# 52_MIPI_Panel.net
KiCad netlist of a schematic drawn in Altium Designer
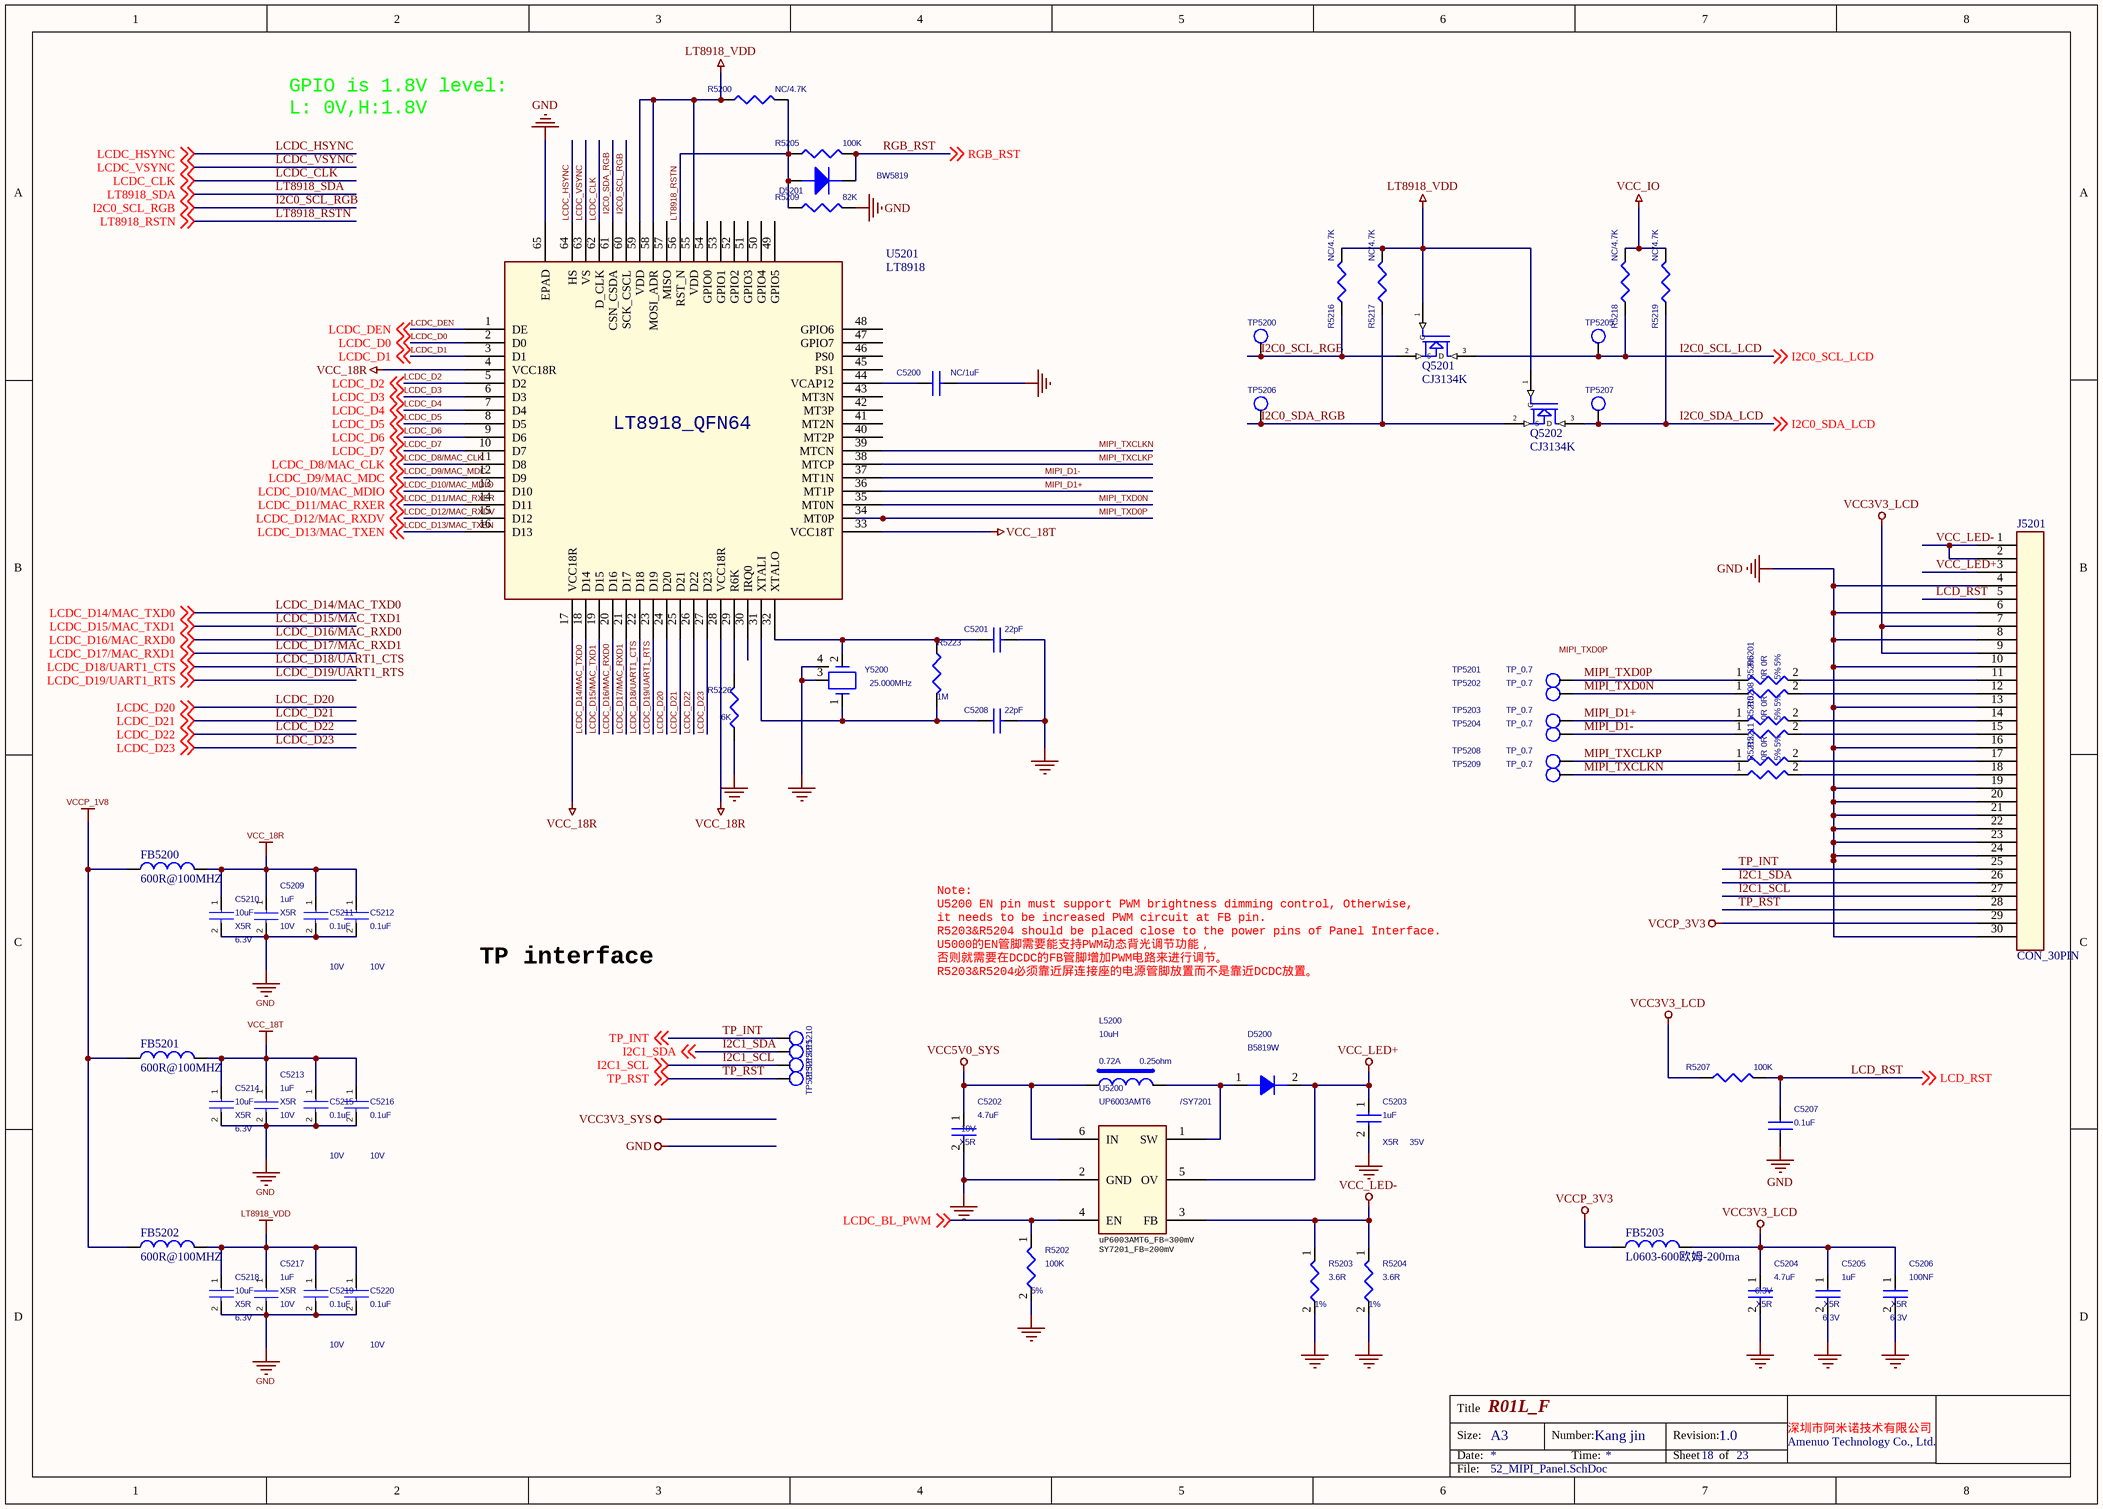
[diagram p0: 52_MIPI_Panel.SchDoc]

(export (version "E")
  (design (tool "Eeschema 10.0.6"))
  (components
    (comp (ref "C5200")
      (value "NC/1uF")
      (footprint "C0402")
      (fields (field (name "PART NUMBER") "117-00-3040") (field (name "DESIGNER") "Hujin"))
      (libsource (lib "*") (part "CAP_NP0603"))
    )
    (comp (ref "C5201")
      (value "22pF")
      (footprint "C0402")
      (fields (field (name "PART NUMBER") "117-00-3002") (field (name "DESIGNER") "Hujin"))
      (libsource (lib "*") (part "CAP_NP0603_Dup1"))
    )
    (comp (ref "C5202")
      (value "4.7uF")
      (footprint "C0603")
      (description "cap,4.70uF,+/-10%,10V,X5R,C0603")
      (fields
        (field (name "VOLTAGE") "10V")
        (field (name "DIELECTRIC") "X5R")
        (field (name "MANUFACTURER") "TDK")
        (field (name "TOLERANCE") "10%")
        (field (name "CREATED BY") "JJJ")
      )
      (libsource (lib "*") (part "CAP NP_Dup1"))
    )
    (comp (ref "C5203")
      (value "1uF")
      (footprint "C0402")
      (description "cap,1.00uF,+/-10%,35V,X5R,C0402")
      (fields
        (field (name "VOLTAGE") "35V")
        (field (name "DIELECTRIC") "X5R")
        (field (name "MANUFACTURER") "TDK")
        (field (name "TOLERANCE") "10%")
        (field (name "CREATED BY") "JJJ")
      )
      (libsource (lib "*") (part "CAP NP_Dup1"))
    )
    (comp (ref "C5204")
      (value "4.7uF")
      (footprint "C0402")
      (description "cap,4.70uF,+/-10%,6.3V,X5R,C0402")
      (fields
        (field (name "VOLTAGE") "6.3V")
        (field (name "DIELECTRIC") "X5R")
        (field (name "TOLERANCE") "10%")
        (field (name "MANUFACTURER") "TDK")
        (field (name "CREATED BY") "JJJ")
      )
      (libsource (lib "*") (part "CAP NP_Dup1"))
    )
    (comp (ref "C5205")
      (value "1uF")
      (footprint "C0402")
      (description "cap,1.00uF,+/-10%,6.3V,X5R,C0402")
      (fields
        (field (name "VOLTAGE") "6.3V")
        (field (name "DIELECTRIC") "X5R")
        (field (name "MANUFACTURER") "TDK")
        (field (name "TOLERANCE") "10%")
        (field (name "CREATED BY") "JJJ")
      )
      (libsource (lib "*") (part "CAP NP_Dup1"))
    )
    (comp (ref "C5206")
      (value "100NF")
      (footprint "C0402")
      (description "cap,100.00nF,+/-10%,6.3V,X5R,C0402")
      (fields
        (field (name "VOLTAGE") "6.3V")
        (field (name "DIELECTRIC") "X5R")
        (field (name "MANUFACTURER") "TDK")
        (field (name "TOLERANCE") "10%")
        (field (name "CREATED BY") "JJJ")
      )
      (libsource (lib "*") (part "CAP NP_Dup1"))
    )
    (comp (ref "C5207")
      (value "0.1uF")
      (footprint "C0402")
      (description "贴片电容")
      (libsource (lib "") (part "CAP NP_Dup1_1"))
    )
    (comp (ref "C5208")
      (value "22pF")
      (footprint "C0402")
      (fields (field (name "PART NUMBER") "117-00-3002") (field (name "DESIGNER") "Hujin"))
      (libsource (lib "*") (part "CAP_NP0603_Dup1"))
    )
    (comp (ref "C5209")
      (value "1uF")
      (footprint "C0402")
      (description "cap,1.00uF,+/-10%,10V,X5R,C0402")
      (fields
        (field (name "VOLTAGE") "10V")
        (field (name "MANUFACTURER") "TDK")
        (field (name "TOLERANCE") "10%")
        (field (name "DIELECTRIC") "X5R")
        (field (name "CREATED_BY") "JJJ")
      )
      (libsource (lib "*") (part "CAP_NP_2"))
    )
    (comp (ref "C5210")
      (value "10uF")
      (footprint "C0603")
      (description "cap,10.00uF,+/-10%,6.3V,X5R,C0603")
      (fields
        (field (name "DIELECTRIC") "X5R")
        (field (name "VOLTAGE") "6.3V")
        (field (name "TOLERANCE") "10%")
        (field (name "MANUFACTURER") "TDK")
        (field (name "CREATED_BY") "JJJ")
      )
      (libsource (lib "*") (part "CAP_NP_2"))
    )
    (comp (ref "C5211")
      (value "0.1uF")
      (footprint "C0402")
      (description "cap,0.1uF,+/-10%,10V,X5R,C0402")
      (fields
        (field (name "TOLERANCE") "10%")
        (field (name "MANUFACTURER") "TDK")
        (field (name "VOLTAGE") "10V")
        (field (name "CREATED_BY") "JJJ")
      )
      (libsource (lib "*") (part "CAP_NP_2"))
    )
    (comp (ref "C5212")
      (value "0.1uF")
      (footprint "C0402")
      (description "cap,0.1uF,+/-10%,10V,X5R,C0402")
      (fields
        (field (name "TOLERANCE") "10%")
        (field (name "MANUFACTURER") "TDK")
        (field (name "VOLTAGE") "10V")
        (field (name "CREATED_BY") "JJJ")
      )
      (libsource (lib "*") (part "CAP_NP_2"))
    )
    (comp (ref "C5213")
      (value "1uF")
      (footprint "C0402")
      (description "cap,1.00uF,+/-10%,10V,X5R,C0402")
      (fields
        (field (name "VOLTAGE") "10V")
        (field (name "MANUFACTURER") "TDK")
        (field (name "TOLERANCE") "10%")
        (field (name "DIELECTRIC") "X5R")
        (field (name "CREATED_BY") "JJJ")
      )
      (libsource (lib "*") (part "CAP_NP_2"))
    )
    (comp (ref "C5214")
      (value "10uF")
      (footprint "C0603")
      (description "cap,10.00uF,+/-10%,6.3V,X5R,C0603")
      (fields
        (field (name "DIELECTRIC") "X5R")
        (field (name "VOLTAGE") "6.3V")
        (field (name "TOLERANCE") "10%")
        (field (name "MANUFACTURER") "TDK")
        (field (name "CREATED_BY") "JJJ")
      )
      (libsource (lib "*") (part "CAP_NP_2"))
    )
    (comp (ref "C5215")
      (value "0.1uF")
      (footprint "C0402")
      (description "cap,0.1uF,+/-10%,10V,X5R,C0402")
      (fields
        (field (name "TOLERANCE") "10%")
        (field (name "MANUFACTURER") "TDK")
        (field (name "VOLTAGE") "10V")
        (field (name "CREATED_BY") "JJJ")
      )
      (libsource (lib "*") (part "CAP_NP_2"))
    )
    (comp (ref "C5216")
      (value "0.1uF")
      (footprint "C0402")
      (description "cap,0.1uF,+/-10%,10V,X5R,C0402")
      (fields
        (field (name "TOLERANCE") "10%")
        (field (name "MANUFACTURER") "TDK")
        (field (name "VOLTAGE") "10V")
        (field (name "CREATED_BY") "JJJ")
      )
      (libsource (lib "*") (part "CAP_NP_2"))
    )
    (comp (ref "C5217")
      (value "1uF")
      (footprint "C0402")
      (description "cap,1.00uF,+/-10%,10V,X5R,C0402")
      (fields
        (field (name "VOLTAGE") "10V")
        (field (name "MANUFACTURER") "TDK")
        (field (name "TOLERANCE") "10%")
        (field (name "DIELECTRIC") "X5R")
        (field (name "CREATED_BY") "JJJ")
      )
      (libsource (lib "*") (part "CAP_NP_2"))
    )
    (comp (ref "C5218")
      (value "10uF")
      (footprint "C0603")
      (description "cap,10.00uF,+/-10%,6.3V,X5R,C0603")
      (fields
        (field (name "DIELECTRIC") "X5R")
        (field (name "VOLTAGE") "6.3V")
        (field (name "TOLERANCE") "10%")
        (field (name "MANUFACTURER") "TDK")
        (field (name "CREATED_BY") "JJJ")
      )
      (libsource (lib "*") (part "CAP_NP_2"))
    )
    (comp (ref "C5219")
      (value "0.1uF")
      (footprint "C0402")
      (description "cap,0.1uF,+/-10%,10V,X5R,C0402")
      (fields
        (field (name "TOLERANCE") "10%")
        (field (name "MANUFACTURER") "TDK")
        (field (name "VOLTAGE") "10V")
        (field (name "CREATED_BY") "JJJ")
      )
      (libsource (lib "*") (part "CAP_NP_2"))
    )
    (comp (ref "C5220")
      (value "0.1uF")
      (footprint "C0402")
      (description "cap,0.1uF,+/-10%,10V,X5R,C0402")
      (fields
        (field (name "TOLERANCE") "10%")
        (field (name "MANUFACTURER") "TDK")
        (field (name "VOLTAGE") "10V")
        (field (name "CREATED_BY") "JJJ")
      )
      (libsource (lib "*") (part "CAP_NP_2"))
    )
    (comp (ref "D5200")
      (value "B5819W")
      (footprint "SOD123")
      (description "Schottky Barrier，B5819W SOD-123")
      (fields (field (name "MANUFACTURER") "长电") (field (name "CREATED BY") "JJJ"))
      (libsource (lib "*") (part "DIODE_Dup1"))
    )
    (comp (ref "D5201")
      (value "BW5819")
      (footprint "SOD-323")
      (description "Diode DO-214AA SMA")
      (fields (field (name "MANUFACTURER") "Diodes") (field (name "MANUFACTURER PART NUMBER") "B220/A"))
      (libsource (lib "*") (part "DIODE"))
    )
    (comp (ref "FB5200")
      (value "600R@100MHZ")
      (footprint "L0402")
      (description "磁珠;600R@100MHZ;0.34R;0.45A;0402;贴片;")
      (libsource (lib "amenuo") (part "INDUCTOR"))
    )
    (comp (ref "FB5201")
      (value "600R@100MHZ")
      (footprint "L0402")
      (description "磁珠;600R@100MHZ;0.34R;0.45A;0402;贴片;")
      (libsource (lib "amenuo") (part "INDUCTOR"))
    )
    (comp (ref "FB5202")
      (value "600R@100MHZ")
      (footprint "L0402")
      (description "磁珠;600R@100MHZ;0.34R;0.45A;0402;贴片;")
      (libsource (lib "amenuo") (part "INDUCTOR"))
    )
    (comp (ref "FB5203")
      (value "L0603-600欧姆-200ma")
      (footprint "L0402")
      (description "L0603-0欧姆-1A")
      (libsource (lib "amenuo") (part "INDUCTOR"))
    )
    (comp (ref "J5201")
      (value "CON_30PIN")
      (footprint "X05A10H30G")
      (libsource (lib "amenuo") (part "CON_30PIN"))
    )
    (comp (ref "L5200")
      (value "10uH")
      (footprint "IND-3X3")
      (description "Power Inductor,10uH,0.2,IND_303015")
      (fields
        (field (name "DC RESISTOR") "0.25ohm")
        (field (name "ISAT") "0.72A")
        (field (name "MANUFACTURER") "sunlord")
        (field (name "TOLERANCE") "20%")
        (field (name "CREATED BY") "YTL")
      )
      (libsource (lib "*") (part "INDUCTORS OF FERRITE"))
    )
    (comp (ref "Q5201") (value "CJ3134K") (footprint "SOT23") (libsource (lib "amenuo") (part "MOSFET-2S3D")))
    (comp (ref "Q5202") (value "CJ3134K") (footprint "SOT23") (libsource (lib "amenuo") (part "MOSFET-2S3D")))
    (comp (ref "R5200")
      (value "NC/4.7K")
      (footprint "R0402")
      (description "贴片电阻")
      (libsource (lib "*") (part "RESISTOR_1"))
    )
    (comp (ref "R5201")
      (value "0R")
      (footprint "R0402")
      (description "通用厚膜电阻,0R,+/-5%,R0402,1/16W.")
      (fields
        (field (name "TOLERANCE") "5%")
        (field (name "MANUFACTURER") "YAGEO")
        (field (name "CREATED BY") "YTL")
      )
      (libsource (lib "*") (part "RESISTOR_Dup1"))
    )
    (comp (ref "R5202")
      (value "100K")
      (footprint "R0402")
      (description "通用厚膜电阻,100K,+/-5%,R0402,1/16W.")
      (fields
        (field (name "TOLERANCE") "5%")
        (field (name "MANUFACTURER") "YAGEO")
        (field (name "CREATED BY") "YTL")
      )
      (libsource (lib "*") (part "RESISTOR_Dup1"))
    )
    (comp (ref "R5203")
      (value "3.6R")
      (footprint "R0402")
      (description "通用厚膜电阻,3R6,+/-1%,R0603,1/10W.")
      (fields
        (field (name "TOLERANCE") "1%")
        (field (name "MANUFACTURER") "YAGEO")
        (field (name "CREATED BY") "YTL")
      )
      (libsource (lib "*") (part "RESISTOR_Dup1"))
    )
    (comp (ref "R5204")
      (value "3.6R")
      (footprint "R0402")
      (description "通用厚膜电阻,3R6,+/-1%,R0603,1/10W.")
      (fields
        (field (name "TOLERANCE") "1%")
        (field (name "MANUFACTURER") "YAGEO")
        (field (name "CREATED BY") "YTL")
      )
      (libsource (lib "*") (part "RESISTOR_Dup1"))
    )
    (comp (ref "R5205")
      (value "100K")
      (footprint "R0402")
      (description "贴片电阻")
      (libsource (lib "*") (part "RESISTOR_1"))
    )
    (comp (ref "R5206")
      (value "0R")
      (footprint "R0402")
      (description "通用厚膜电阻,0R,+/-5%,R0402,1/16W.")
      (fields
        (field (name "TOLERANCE") "5%")
        (field (name "MANUFACTURER") "YAGEO")
        (field (name "CREATED BY") "YTL")
      )
      (libsource (lib "*") (part "RESISTOR_Dup1"))
    )
    (comp (ref "R5207")
      (value "100K")
      (footprint "R0402")
      (description "贴片电阻")
      (libsource (lib "*") (part "RESISTOR_1"))
    )
    (comp (ref "R5208")
      (value "0R")
      (footprint "R0402")
      (description "通用厚膜电阻,0R,+/-5%,R0402,1/16W.")
      (fields
        (field (name "TOLERANCE") "5%")
        (field (name "MANUFACTURER") "YAGEO")
        (field (name "CREATED BY") "YTL")
      )
      (libsource (lib "*") (part "RESISTOR_Dup1"))
    )
    (comp (ref "R5209")
      (value "82K")
      (footprint "R0402")
      (description "贴片电阻")
      (libsource (lib "*") (part "RESISTOR_1"))
    )
    (comp (ref "R5210")
      (value "0R")
      (footprint "R0402")
      (description "通用厚膜电阻,0R,+/-5%,R0402,1/16W.")
      (fields
        (field (name "TOLERANCE") "5%")
        (field (name "MANUFACTURER") "YAGEO")
        (field (name "CREATED BY") "YTL")
      )
      (libsource (lib "*") (part "RESISTOR_Dup1"))
    )
    (comp (ref "R5211")
      (value "0R")
      (footprint "R0402")
      (description "通用厚膜电阻,0R,+/-5%,R0402,1/16W.")
      (fields
        (field (name "TOLERANCE") "5%")
        (field (name "MANUFACTURER") "YAGEO")
        (field (name "CREATED BY") "YTL")
      )
      (libsource (lib "*") (part "RESISTOR_Dup1"))
    )
    (comp (ref "R5212")
      (value "0R")
      (footprint "R0402")
      (description "通用厚膜电阻,0R,+/-5%,R0402,1/16W.")
      (fields
        (field (name "TOLERANCE") "5%")
        (field (name "MANUFACTURER") "YAGEO")
        (field (name "CREATED BY") "YTL")
      )
      (libsource (lib "*") (part "RESISTOR_Dup1"))
    )
    (comp (ref "R5216")
      (value "NC/4.7K")
      (footprint "R0402")
      (description "贴片电阻")
      (libsource (lib "*") (part "RESISTOR_1"))
    )
    (comp (ref "R5217")
      (value "NC/4.7K")
      (footprint "R0402")
      (description "贴片电阻")
      (libsource (lib "*") (part "RESISTOR_1"))
    )
    (comp (ref "R5218")
      (value "NC/4.7K")
      (footprint "R0402")
      (description "贴片电阻")
      (libsource (lib "*") (part "RESISTOR_1"))
    )
    (comp (ref "R5219")
      (value "NC/4.7K")
      (footprint "R0402")
      (description "贴片电阻")
      (libsource (lib "*") (part "RESISTOR_1"))
    )
    (comp (ref "R5223")
      (value "1M")
      (footprint "R0402")
      (fields (field (name "PART NUMBER") "737-00-3074") (field (name "DESIGNER") "Hujin"))
      (libsource (lib "*") (part "RES0603_Dup3"))
    )
    (comp (ref "R5226")
      (value "6K")
      (footprint "R0402")
      (fields
        (field (name "TOLERANCE") "%5")
        (field (name "PART NUMBER") "737-00-3049")
        (field (name "DESIGNER") "Hujin")
      )
      (libsource (lib "*") (part "RES0603_Dup2"))
    )
    (comp (ref "TP5200")
      (value "TP_0.7")
      (footprint "TEST")
      (description "Test Point 0.7mm")
      (fields (field (name "CREATED BY") "JJJ"))
      (libsource (lib "*") (part "TP"))
    )
    (comp (ref "TP5201")
      (value "TP_0.7")
      (footprint "TP")
      (fields (field (name "CREATED BY") "JJJ"))
      (libsource (lib "*") (part "TP"))
    )
    (comp (ref "TP5202")
      (value "TP_0.7")
      (footprint "TP")
      (fields (field (name "CREATED BY") "JJJ"))
      (libsource (lib "*") (part "TP"))
    )
    (comp (ref "TP5203")
      (value "TP_0.7")
      (footprint "TP")
      (fields (field (name "CREATED BY") "JJJ"))
      (libsource (lib "*") (part "TP"))
    )
    (comp (ref "TP5204")
      (value "TP_0.7")
      (footprint "TP")
      (fields (field (name "CREATED BY") "JJJ"))
      (libsource (lib "*") (part "TP"))
    )
    (comp (ref "TP5205")
      (value "TP_0.7")
      (footprint "TEST")
      (description "Test Point 0.7mm")
      (fields (field (name "CREATED BY") "JJJ"))
      (libsource (lib "*") (part "TP"))
    )
    (comp (ref "TP5206")
      (value "TP_0.7")
      (footprint "TEST")
      (description "Test Point 0.7mm")
      (fields (field (name "CREATED BY") "JJJ"))
      (libsource (lib "*") (part "TP"))
    )
    (comp (ref "TP5207")
      (value "TP_0.7")
      (footprint "TEST")
      (description "Test Point 0.7mm")
      (fields (field (name "CREATED BY") "JJJ"))
      (libsource (lib "*") (part "TP"))
    )
    (comp (ref "TP5208")
      (value "TP_0.7")
      (footprint "TP")
      (fields (field (name "CREATED BY") "JJJ"))
      (libsource (lib "*") (part "TP"))
    )
    (comp (ref "TP5209")
      (value "TP_0.7")
      (footprint "TP")
      (fields (field (name "CREATED BY") "JJJ"))
      (libsource (lib "*") (part "TP"))
    )
    (comp (ref "TP5210")
      (value "TP_0.7")
      (footprint "TEST")
      (description "Test Point 0.7mm")
      (fields (field (name "CREATED BY") "JJJ"))
      (libsource (lib "*") (part "TP"))
    )
    (comp (ref "TP5211")
      (value "TP_0.7")
      (footprint "TEST")
      (description "Test Point 0.7mm")
      (fields (field (name "CREATED BY") "JJJ"))
      (libsource (lib "*") (part "TP"))
    )
    (comp (ref "TP5212")
      (value "TP_0.7")
      (footprint "TEST")
      (description "Test Point 0.7mm")
      (fields (field (name "CREATED BY") "JJJ"))
      (libsource (lib "*") (part "TP"))
    )
    (comp (ref "TP5213")
      (value "TP_0.7")
      (footprint "TEST")
      (description "Test Point 0.7mm")
      (fields (field (name "CREATED BY") "JJJ"))
      (libsource (lib "*") (part "TP"))
    )
    (comp (ref "U5200")
      (value "UP6003AMT6")
      (footprint "SOT-23-6")
      (description "Tiny Package, High Performance, Constant Current Switching Regulator for 10X White LED")
      (fields
        (field (name "MANUFACTURER") "UPI(力智电子)")
        (field (name "OPTION") "/SY7201")
        (field (name "CREATED BY") "JJJ")
      )
      (libsource (lib "*") (part "DCDC_MP1488"))
    )
    (comp (ref "U5201")
      (value "LT8918")
      (footprint "LT8918_QFN64_EPAD")
      (libsource (lib "amenuo") (part "LT8918"))
    )
    (comp (ref "Y5200") (value "25.000MHz") (footprint "SMD_3225") (libsource (lib "*") (part "CRYSTAL_0")))
  )
  (nets
    (net (code "1") (name "/I2C0_SDA_RGB") (class "Default")
      (node (ref "Q5202") (pin "2") (pinfunction "S_2") (pintype "input"))
      (node (ref "R5217") (pin "1") (pinfunction "1_1") (pintype "passive"))
      (node (ref "TP5206") (pin "1") (pinfunction "1_1") (pintype "passive"))
      (node (ref "U5201") (pin "61") (pinfunction "CSN_CSDA_61") (pintype "passive"))
    )
    (net (code "2") (name "/MIPI_D1+") (class "Default")
      (node (ref "R5208") (pin "1") (pinfunction "1_1") (pintype "passive"))
      (node (ref "TP5203") (pin "1") (pinfunction "1_1") (pintype "passive"))
      (node (ref "U5201") (pin "36") (pinfunction "MT1P_36") (pintype "passive"))
    )
    (net (code "3") (name "/MIPI_D1-") (class "Default")
      (node (ref "R5210") (pin "1") (pinfunction "1_1") (pintype "passive"))
      (node (ref "TP5204") (pin "1") (pinfunction "1_1") (pintype "passive"))
      (node (ref "U5201") (pin "37") (pinfunction "MT1N_37") (pintype "passive"))
    )
    (net (code "4") (name "/MIPI_TXCLKN") (class "Default")
      (node (ref "R5212") (pin "1") (pinfunction "1_1") (pintype "passive"))
      (node (ref "TP5209") (pin "1") (pinfunction "1_1") (pintype "passive"))
      (node (ref "U5201") (pin "39") (pinfunction "MTCN_39") (pintype "passive"))
    )
    (net (code "5") (name "/MIPI_TXCLKP") (class "Default")
      (node (ref "R5211") (pin "1") (pinfunction "1_1") (pintype "passive"))
      (node (ref "TP5208") (pin "1") (pinfunction "1_1") (pintype "passive"))
      (node (ref "U5201") (pin "38") (pinfunction "MTCP_38") (pintype "passive"))
    )
    (net (code "6") (name "/MIPI_TXD0N") (class "Default")
      (node (ref "R5206") (pin "1") (pinfunction "1_1") (pintype "passive"))
      (node (ref "TP5202") (pin "1") (pinfunction "1_1") (pintype "passive"))
      (node (ref "U5201") (pin "35") (pinfunction "MT0N_35") (pintype "passive"))
    )
    (net (code "7") (name "/MIPI_TXD0P") (class "Default")
      (node (ref "R5201") (pin "1") (pinfunction "1_1") (pintype "passive"))
      (node (ref "TP5201") (pin "1") (pinfunction "1_1") (pintype "passive"))
      (node (ref "U5201") (pin "34") (pinfunction "MT0P_34") (pintype "passive"))
    )
    (net (code "8") (name "GND") (class "Default")
      (node (ref "C5200") (pin "2") (pinfunction "2_2") (pintype "passive"))
      (node (ref "C5201") (pin "2") (pinfunction "2_2") (pintype "passive"))
      (node (ref "C5202") (pin "2") (pinfunction "2_2") (pintype "passive"))
      (node (ref "C5203") (pin "2") (pinfunction "2_2") (pintype "passive"))
      (node (ref "C5204") (pin "2") (pinfunction "2_2") (pintype "passive"))
      (node (ref "C5205") (pin "2") (pinfunction "2_2") (pintype "passive"))
      (node (ref "C5206") (pin "2") (pinfunction "2_2") (pintype "passive"))
      (node (ref "C5207") (pin "2") (pinfunction "2_2") (pintype "passive"))
      (node (ref "C5208") (pin "2") (pinfunction "2_2") (pintype "passive"))
      (node (ref "C5209") (pin "2") (pinfunction "2_2") (pintype "passive"))
      (node (ref "C5210") (pin "2") (pinfunction "2_2") (pintype "passive"))
      (node (ref "C5211") (pin "2") (pinfunction "2_2") (pintype "passive"))
      (node (ref "C5212") (pin "2") (pinfunction "2_2") (pintype "passive"))
      (node (ref "C5213") (pin "2") (pinfunction "2_2") (pintype "passive"))
      (node (ref "C5214") (pin "2") (pinfunction "2_2") (pintype "passive"))
      (node (ref "C5215") (pin "2") (pinfunction "2_2") (pintype "passive"))
      (node (ref "C5216") (pin "2") (pinfunction "2_2") (pintype "passive"))
      (node (ref "C5217") (pin "2") (pinfunction "2_2") (pintype "passive"))
      (node (ref "C5218") (pin "2") (pinfunction "2_2") (pintype "passive"))
      (node (ref "C5219") (pin "2") (pinfunction "2_2") (pintype "passive"))
      (node (ref "C5220") (pin "2") (pinfunction "2_2") (pintype "passive"))
      (node (ref "J5201") (pin "10") (pinfunction "10_10") (pintype "passive"))
      (node (ref "J5201") (pin "13") (pinfunction "13_13") (pintype "passive"))
      (node (ref "J5201") (pin "16") (pinfunction "16_16") (pintype "passive"))
      (node (ref "J5201") (pin "19") (pinfunction "19_19") (pintype "passive"))
      (node (ref "J5201") (pin "20") (pinfunction "20_20") (pintype "passive"))
      (node (ref "J5201") (pin "21") (pinfunction "21_21") (pintype "passive"))
      (node (ref "J5201") (pin "22") (pinfunction "22_22") (pintype "passive"))
      (node (ref "J5201") (pin "23") (pinfunction "23_23") (pintype "passive"))
      (node (ref "J5201") (pin "24") (pinfunction "24_24") (pintype "passive"))
      (node (ref "J5201") (pin "30") (pinfunction "30_30") (pintype "passive"))
      (node (ref "J5201") (pin "4") (pinfunction "4_4") (pintype "passive"))
      (node (ref "J5201") (pin "6") (pinfunction "6_6") (pintype "passive"))
      (node (ref "J5201") (pin "8") (pinfunction "8_8") (pintype "passive"))
      (node (ref "R5202") (pin "2") (pinfunction "2_2") (pintype "passive"))
      (node (ref "R5203") (pin "2") (pinfunction "2_2") (pintype "passive"))
      (node (ref "R5204") (pin "2") (pinfunction "2_2") (pintype "passive"))
      (node (ref "R5209") (pin "2") (pinfunction "2_2") (pintype "passive"))
      (node (ref "R5226") (pin "1") (pinfunction "1_1") (pintype "passive"))
      (node (ref "U5200") (pin "2") (pinfunction "GND_2") (pintype "passive"))
      (node (ref "U5201") (pin "65") (pinfunction "EPAD_65") (pintype "power_in"))
      (node (ref "Y5200") (pin "3") (pinfunction "3_3") (pintype "passive"))
      (node (ref "Y5200") (pin "4") (pinfunction "4_4") (pintype "passive"))
    )
    (net (code "9") (name "I2C0_SCL_LCD") (class "Default")
      (node (ref "Q5201") (pin "3") (pinfunction "D_3") (pintype "input"))
      (node (ref "R5218") (pin "1") (pinfunction "1_1") (pintype "passive"))
      (node (ref "TP5205") (pin "1") (pinfunction "1_1") (pintype "passive"))
    )
    (net (code "10") (name "I2C0_SCL_RGB") (class "Default")
      (node (ref "Q5201") (pin "2") (pinfunction "S_2") (pintype "input"))
      (node (ref "R5216") (pin "1") (pinfunction "1_1") (pintype "passive"))
      (node (ref "TP5200") (pin "1") (pinfunction "1_1") (pintype "passive"))
      (node (ref "U5201") (pin "60") (pinfunction "SCK_CSCL_60") (pintype "passive"))
    )
    (net (code "11") (name "I2C0_SDA_LCD") (class "Default")
      (node (ref "Q5202") (pin "3") (pinfunction "D_3") (pintype "input"))
      (node (ref "R5219") (pin "1") (pinfunction "1_1") (pintype "passive"))
      (node (ref "TP5207") (pin "1") (pinfunction "1_1") (pintype "passive"))
    )
    (net (code "12") (name "I2C1_SCL") (class "Default")
      (node (ref "J5201") (pin "27") (pinfunction "27_27") (pintype "passive"))
      (node (ref "TP5212") (pin "1") (pinfunction "1_1") (pintype "passive"))
    )
    (net (code "13") (name "I2C1_SDA") (class "Default")
      (node (ref "J5201") (pin "26") (pinfunction "26_26") (pintype "passive"))
      (node (ref "TP5211") (pin "1") (pinfunction "1_1") (pintype "passive"))
    )
    (net (code "14") (name "LCDC_BL_PWM") (class "Default")
      (node (ref "R5202") (pin "1") (pinfunction "1_1") (pintype "passive"))
      (node (ref "U5200") (pin "4") (pinfunction "EN_4") (pintype "passive"))
    )
    (net (code "15") (name "LCDC_CLK") (class "Default")
      (node (ref "U5201") (pin "62") (pinfunction "D_CLK_62") (pintype "power_in"))
    )
    (net (code "16") (name "LCDC_D0") (class "Default")
      (node (ref "U5201") (pin "2") (pinfunction "D0_2") (pintype "passive"))
    )
    (net (code "17") (name "LCDC_D1") (class "Default")
      (node (ref "U5201") (pin "3") (pinfunction "D1_3") (pintype "power_in"))
    )
    (net (code "18") (name "LCDC_D2") (class "Default")
      (node (ref "U5201") (pin "5") (pinfunction "D2_5") (pintype "passive"))
    )
    (net (code "19") (name "LCDC_D3") (class "Default")
      (node (ref "U5201") (pin "6") (pinfunction "D3_6") (pintype "passive"))
    )
    (net (code "20") (name "LCDC_D4") (class "Default")
      (node (ref "U5201") (pin "7") (pinfunction "D4_7") (pintype "passive"))
    )
    (net (code "21") (name "LCDC_D5") (class "Default")
      (node (ref "U5201") (pin "8") (pinfunction "D5_8") (pintype "passive"))
    )
    (net (code "22") (name "LCDC_D6") (class "Default")
      (node (ref "U5201") (pin "9") (pinfunction "D6_9") (pintype "passive"))
    )
    (net (code "23") (name "LCDC_D7") (class "Default")
      (node (ref "U5201") (pin "10") (pinfunction "D7_10") (pintype "passive"))
    )
    (net (code "24") (name "LCDC_D8{slash}MAC_CLK") (class "Default")
      (node (ref "U5201") (pin "11") (pinfunction "D8_11") (pintype "passive"))
    )
    (net (code "25") (name "LCDC_D9{slash}MAC_MDC") (class "Default")
      (node (ref "U5201") (pin "12") (pinfunction "D9_12") (pintype "passive"))
    )
    (net (code "26") (name "LCDC_D10{slash}MAC_MDIO") (class "Default")
      (node (ref "U5201") (pin "13") (pinfunction "D10_13") (pintype "passive"))
    )
    (net (code "27") (name "LCDC_D11{slash}MAC_RXER") (class "Default")
      (node (ref "U5201") (pin "14") (pinfunction "D11_14") (pintype "passive"))
    )
    (net (code "28") (name "LCDC_D12{slash}MAC_RXDV") (class "Default")
      (node (ref "U5201") (pin "15") (pinfunction "D12_15") (pintype "passive"))
    )
    (net (code "29") (name "LCDC_D13{slash}MAC_TXEN") (class "Default")
      (node (ref "U5201") (pin "16") (pinfunction "D13_16") (pintype "passive"))
    )
    (net (code "30") (name "LCDC_D14{slash}MAC_TXD0") (class "Default")
      (node (ref "U5201") (pin "18") (pinfunction "D14_18") (pintype "passive"))
    )
    (net (code "31") (name "LCDC_D15{slash}MAC_TXD1") (class "Default")
      (node (ref "U5201") (pin "19") (pinfunction "D15_19") (pintype "passive"))
    )
    (net (code "32") (name "LCDC_D16{slash}MAC_RXD0") (class "Default")
      (node (ref "U5201") (pin "20") (pinfunction "D16_20") (pintype "passive"))
    )
    (net (code "33") (name "LCDC_D17{slash}MAC_RXD1") (class "Default")
      (node (ref "U5201") (pin "21") (pinfunction "D17_21") (pintype "passive"))
    )
    (net (code "34") (name "LCDC_D18{slash}UART1_CTS") (class "Default")
      (node (ref "U5201") (pin "22") (pinfunction "D18_22") (pintype "passive"))
    )
    (net (code "35") (name "LCDC_D19{slash}UART1_RTS") (class "Default")
      (node (ref "U5201") (pin "23") (pinfunction "D19_23") (pintype "passive"))
    )
    (net (code "36") (name "LCDC_D20") (class "Default")
      (node (ref "U5201") (pin "24") (pinfunction "D20_24") (pintype "passive"))
    )
    (net (code "37") (name "LCDC_D21") (class "Default")
      (node (ref "U5201") (pin "25") (pinfunction "D21_25") (pintype "passive"))
    )
    (net (code "38") (name "LCDC_D22") (class "Default")
      (node (ref "U5201") (pin "26") (pinfunction "D22_26") (pintype "passive"))
    )
    (net (code "39") (name "LCDC_D23") (class "Default")
      (node (ref "U5201") (pin "27") (pinfunction "D23_27") (pintype "passive"))
    )
    (net (code "40") (name "LCDC_DEN") (class "Default")
      (node (ref "U5201") (pin "1") (pinfunction "DE_1") (pintype "power_in"))
    )
    (net (code "41") (name "LCDC_HSYNC") (class "Default")
      (node (ref "U5201") (pin "64") (pinfunction "HS_64") (pintype "power_in"))
    )
    (net (code "42") (name "LCDC_VSYNC") (class "Default")
      (node (ref "U5201") (pin "63") (pinfunction "VS_63") (pintype "passive"))
    )
    (net (code "43") (name "LCD_RST") (class "Default")
      (node (ref "C5207") (pin "1") (pinfunction "1_1") (pintype "passive"))
      (node (ref "J5201") (pin "5") (pinfunction "5_5") (pintype "passive"))
      (node (ref "R5207") (pin "2") (pinfunction "2_2") (pintype "passive"))
    )
    (net (code "44") (name "LT8918_RSTN") (class "Default")
      (node (ref "D5201") (pin "1") (pinfunction "+_1") (pintype "passive"))
      (node (ref "R5200") (pin "2") (pinfunction "2_2") (pintype "passive"))
      (node (ref "R5205") (pin "1") (pinfunction "1_1") (pintype "passive"))
      (node (ref "R5209") (pin "1") (pinfunction "1_1") (pintype "passive"))
      (node (ref "U5201") (pin "56") (pinfunction "RST_N_56") (pintype "passive"))
    )
    (net (code "46") (name "LT8918_VDD") (class "Default")
      (node (ref "C5217") (pin "1") (pinfunction "1_1") (pintype "passive"))
      (node (ref "C5218") (pin "1") (pinfunction "1_1") (pintype "passive"))
      (node (ref "C5219") (pin "1") (pinfunction "1_1") (pintype "passive"))
      (node (ref "C5220") (pin "1") (pinfunction "1_1") (pintype "passive"))
      (node (ref "FB5202") (pin "2") (pinfunction "2_2") (pintype "passive"))
      (node (ref "Q5201") (pin "1") (pinfunction "G_1") (pintype "input"))
      (node (ref "Q5202") (pin "1") (pinfunction "G_1") (pintype "input"))
      (node (ref "R5200") (pin "1") (pinfunction "1_1") (pintype "passive"))
      (node (ref "R5216") (pin "2") (pinfunction "2_2") (pintype "passive"))
      (node (ref "R5217") (pin "2") (pinfunction "2_2") (pintype "passive"))
      (node (ref "U5201") (pin "55") (pinfunction "VDD_55") (pintype "power_in"))
      (node (ref "U5201") (pin "58") (pinfunction "MOSI_ADR_58") (pintype "passive"))
      (node (ref "U5201") (pin "59") (pinfunction "VDD_59") (pintype "power_in"))
    )
    (net (code "47") (name "Net-(D5200-A)") (class "Default")
      (node (ref "D5200") (pin "1") (pinfunction "A_1") (pintype "passive"))
      (node (ref "L5200") (pin "2") (pinfunction "2_2") (pintype "passive"))
      (node (ref "U5200") (pin "1") (pinfunction "SW_1") (pintype "passive"))
    )
    (net (code "48") (name "Net-(J5201-Pad11)") (class "Default")
      (node (ref "J5201") (pin "11") (pinfunction "11_11") (pintype "passive"))
      (node (ref "R5201") (pin "2") (pinfunction "2_2") (pintype "passive"))
    )
    (net (code "49") (name "Net-(J5201-Pad12)") (class "Default")
      (node (ref "J5201") (pin "12") (pinfunction "12_12") (pintype "passive"))
      (node (ref "R5206") (pin "2") (pinfunction "2_2") (pintype "passive"))
    )
    (net (code "50") (name "Net-(J5201-Pad14)") (class "Default")
      (node (ref "J5201") (pin "14") (pinfunction "14_14") (pintype "passive"))
      (node (ref "R5208") (pin "2") (pinfunction "2_2") (pintype "passive"))
    )
    (net (code "51") (name "Net-(J5201-Pad15)") (class "Default")
      (node (ref "J5201") (pin "15") (pinfunction "15_15") (pintype "passive"))
      (node (ref "R5210") (pin "2") (pinfunction "2_2") (pintype "passive"))
    )
    (net (code "52") (name "Net-(J5201-Pad17)") (class "Default")
      (node (ref "J5201") (pin "17") (pinfunction "17_17") (pintype "passive"))
      (node (ref "R5211") (pin "2") (pinfunction "2_2") (pintype "passive"))
    )
    (net (code "53") (name "Net-(J5201-Pad18)") (class "Default")
      (node (ref "J5201") (pin "18") (pinfunction "18_18") (pintype "passive"))
      (node (ref "R5212") (pin "2") (pinfunction "2_2") (pintype "passive"))
    )
    (net (code "54") (name "Net-(U5201-R6K)") (class "Default")
      (node (ref "R5226") (pin "2") (pinfunction "2_2") (pintype "passive"))
      (node (ref "U5201") (pin "29") (pinfunction "R6K_29") (pintype "passive"))
    )
    (net (code "55") (name "Net-(U5201-VCAP12)") (class "Default")
      (node (ref "C5200") (pin "1") (pinfunction "1_1") (pintype "passive"))
      (node (ref "U5201") (pin "44") (pinfunction "VCAP12_44") (pintype "power_in"))
    )
    (net (code "56") (name "Net-(U5201-XTALI)") (class "Default")
      (node (ref "C5208") (pin "1") (pinfunction "1_1") (pintype "passive"))
      (node (ref "R5223") (pin "2") (pinfunction "2_2") (pintype "passive"))
      (node (ref "U5201") (pin "31") (pinfunction "XTALI_31") (pintype "passive"))
      (node (ref "Y5200") (pin "1") (pinfunction "1_1") (pintype "passive"))
    )
    (net (code "57") (name "Net-(U5201-XTALO)") (class "Default")
      (node (ref "C5201") (pin "1") (pinfunction "1_1") (pintype "passive"))
      (node (ref "R5223") (pin "1") (pinfunction "1_1") (pintype "passive"))
      (node (ref "U5201") (pin "32") (pinfunction "XTALO_32") (pintype "passive"))
      (node (ref "Y5200") (pin "2") (pinfunction "2_2") (pintype "passive"))
    )
    (net (code "58") (name "RGB_RST") (class "Default")
      (node (ref "D5201") (pin "2") (pinfunction "-_2") (pintype "passive"))
      (node (ref "R5205") (pin "2") (pinfunction "2_2") (pintype "passive"))
    )
    (net (code "59") (name "TP_INT") (class "Default")
      (node (ref "J5201") (pin "25") (pinfunction "25_25") (pintype "passive"))
      (node (ref "TP5210") (pin "1") (pinfunction "1_1") (pintype "passive"))
    )
    (net (code "60") (name "TP_RST") (class "Default")
      (node (ref "J5201") (pin "28") (pinfunction "28_28") (pintype "passive"))
      (node (ref "TP5213") (pin "1") (pinfunction "1_1") (pintype "passive"))
    )
    (net (code "61") (name "VCC3V3_LCD") (class "Default")
      (node (ref "C5204") (pin "1") (pinfunction "1_1") (pintype "passive"))
      (node (ref "C5205") (pin "1") (pinfunction "1_1") (pintype "passive"))
      (node (ref "C5206") (pin "1") (pinfunction "1_1") (pintype "passive"))
      (node (ref "FB5203") (pin "2") (pinfunction "2_2") (pintype "passive"))
      (node (ref "J5201") (pin "7") (pinfunction "7_7") (pintype "passive"))
      (node (ref "J5201") (pin "9") (pinfunction "9_9") (pintype "passive"))
      (node (ref "R5207") (pin "1") (pinfunction "1_1") (pintype "passive"))
    )
    (net (code "63") (name "VCC5V0_SYS") (class "Default")
      (node (ref "C5202") (pin "1") (pinfunction "1_1") (pintype "passive"))
      (node (ref "L5200") (pin "1") (pinfunction "1_1") (pintype "passive"))
      (node (ref "U5200") (pin "6") (pinfunction "IN_6") (pintype "passive"))
    )
    (net (code "64") (name "VCCP_1V8") (class "Default")
      (node (ref "FB5200") (pin "1") (pinfunction "1_1") (pintype "passive"))
      (node (ref "FB5201") (pin "1") (pinfunction "1_1") (pintype "passive"))
      (node (ref "FB5202") (pin "1") (pinfunction "1_1") (pintype "passive"))
    )
    (net (code "65") (name "VCCP_3V3") (class "Default")
      (node (ref "FB5203") (pin "1") (pinfunction "1_1") (pintype "passive"))
      (node (ref "J5201") (pin "29") (pinfunction "29_29") (pintype "passive"))
    )
    (net (code "66") (name "VCC_18R") (class "Default")
      (node (ref "C5209") (pin "1") (pinfunction "1_1") (pintype "passive"))
      (node (ref "C5210") (pin "1") (pinfunction "1_1") (pintype "passive"))
      (node (ref "C5211") (pin "1") (pinfunction "1_1") (pintype "passive"))
      (node (ref "C5212") (pin "1") (pinfunction "1_1") (pintype "passive"))
      (node (ref "FB5200") (pin "2") (pinfunction "2_2") (pintype "passive"))
      (node (ref "U5201") (pin "17") (pinfunction "VCC18R_17") (pintype "power_in"))
      (node (ref "U5201") (pin "28") (pinfunction "VCC18R_28") (pintype "power_in"))
      (node (ref "U5201") (pin "4") (pinfunction "VCC18R_4") (pintype "power_in"))
    )
    (net (code "67") (name "VCC_18T") (class "Default")
      (node (ref "C5213") (pin "1") (pinfunction "1_1") (pintype "passive"))
      (node (ref "C5214") (pin "1") (pinfunction "1_1") (pintype "passive"))
      (node (ref "C5215") (pin "1") (pinfunction "1_1") (pintype "passive"))
      (node (ref "C5216") (pin "1") (pinfunction "1_1") (pintype "passive"))
      (node (ref "FB5201") (pin "2") (pinfunction "2_2") (pintype "passive"))
      (node (ref "U5201") (pin "33") (pinfunction "VCC18T_33") (pintype "power_in"))
    )
    (net (code "68") (name "VCC_IO") (class "Default")
      (node (ref "R5218") (pin "2") (pinfunction "2_2") (pintype "passive"))
      (node (ref "R5219") (pin "2") (pinfunction "2_2") (pintype "passive"))
    )
    (net (code "69") (name "VCC_LED+") (class "Default")
      (node (ref "C5203") (pin "1") (pinfunction "1_1") (pintype "passive"))
      (node (ref "D5200") (pin "2") (pinfunction "K_2") (pintype "passive"))
      (node (ref "J5201") (pin "3") (pinfunction "3_3") (pintype "passive"))
      (node (ref "U5200") (pin "5") (pinfunction "OV_5") (pintype "passive"))
    )
    (net (code "70") (name "VCC_LED-") (class "Default")
      (node (ref "J5201") (pin "1") (pinfunction "1_1") (pintype "passive"))
      (node (ref "J5201") (pin "2") (pinfunction "2_2") (pintype "passive"))
      (node (ref "R5203") (pin "1") (pinfunction "1_1") (pintype "passive"))
      (node (ref "R5204") (pin "1") (pinfunction "1_1") (pintype "passive"))
      (node (ref "U5200") (pin "3") (pinfunction "FB_3") (pintype "passive"))
    )
    (net (code "71") (name "unconnected-(U5201-GPIO0-Pad54)") (class "Default")
      (node (ref "U5201") (pin "54") (pinfunction "GPIO0_54") (pintype "passive"))
    )
    (net (code "72") (name "unconnected-(U5201-GPIO1-Pad53)") (class "Default")
      (node (ref "U5201") (pin "53") (pinfunction "GPIO1_53") (pintype "passive"))
    )
    (net (code "73") (name "unconnected-(U5201-GPIO2-Pad52)") (class "Default")
      (node (ref "U5201") (pin "52") (pinfunction "GPIO2_52") (pintype "passive"))
    )
    (net (code "74") (name "unconnected-(U5201-GPIO3-Pad51)") (class "Default")
      (node (ref "U5201") (pin "51") (pinfunction "GPIO3_51") (pintype "passive"))
    )
    (net (code "75") (name "unconnected-(U5201-GPIO4-Pad50)") (class "Default")
      (node (ref "U5201") (pin "50") (pinfunction "GPIO4_50") (pintype "passive"))
    )
    (net (code "76") (name "unconnected-(U5201-GPIO5-Pad49)") (class "Default")
      (node (ref "U5201") (pin "49") (pinfunction "GPIO5_49") (pintype "passive"))
    )
    (net (code "77") (name "unconnected-(U5201-GPIO6-Pad48)") (class "Default")
      (node (ref "U5201") (pin "48") (pinfunction "GPIO6_48") (pintype "passive"))
    )
    (net (code "78") (name "unconnected-(U5201-GPIO7-Pad47)") (class "Default")
      (node (ref "U5201") (pin "47") (pinfunction "GPIO7_47") (pintype "passive"))
    )
    (net (code "79") (name "unconnected-(U5201-IRQ0-Pad30)") (class "Default")
      (node (ref "U5201") (pin "30") (pinfunction "IRQ0_30") (pintype "passive"))
    )
    (net (code "80") (name "unconnected-(U5201-MISO-Pad57)") (class "Default")
      (node (ref "U5201") (pin "57") (pinfunction "MISO_57") (pintype "passive"))
    )
    (net (code "81") (name "unconnected-(U5201-MT2N-Pad41)") (class "Default")
      (node (ref "U5201") (pin "41") (pinfunction "MT2N_41") (pintype "passive"))
    )
    (net (code "82") (name "unconnected-(U5201-MT2P-Pad40)") (class "Default")
      (node (ref "U5201") (pin "40") (pinfunction "MT2P_40") (pintype "passive"))
    )
    (net (code "83") (name "unconnected-(U5201-MT3N-Pad43)") (class "Default")
      (node (ref "U5201") (pin "43") (pinfunction "MT3N_43") (pintype "passive"))
    )
    (net (code "84") (name "unconnected-(U5201-MT3P-Pad42)") (class "Default")
      (node (ref "U5201") (pin "42") (pinfunction "MT3P_42") (pintype "passive"))
    )
    (net (code "85") (name "unconnected-(U5201-PS0-Pad46)") (class "Default")
      (node (ref "U5201") (pin "46") (pinfunction "PS0_46") (pintype "passive"))
    )
    (net (code "86") (name "unconnected-(U5201-PS1-Pad45)") (class "Default")
      (node (ref "U5201") (pin "45") (pinfunction "PS1_45") (pintype "passive"))
    )
  )
)
